# SCH_HomeConv2_mit-IR_2026-09-25.net
KiCad netlist of a schematic drawn in EasyEDA
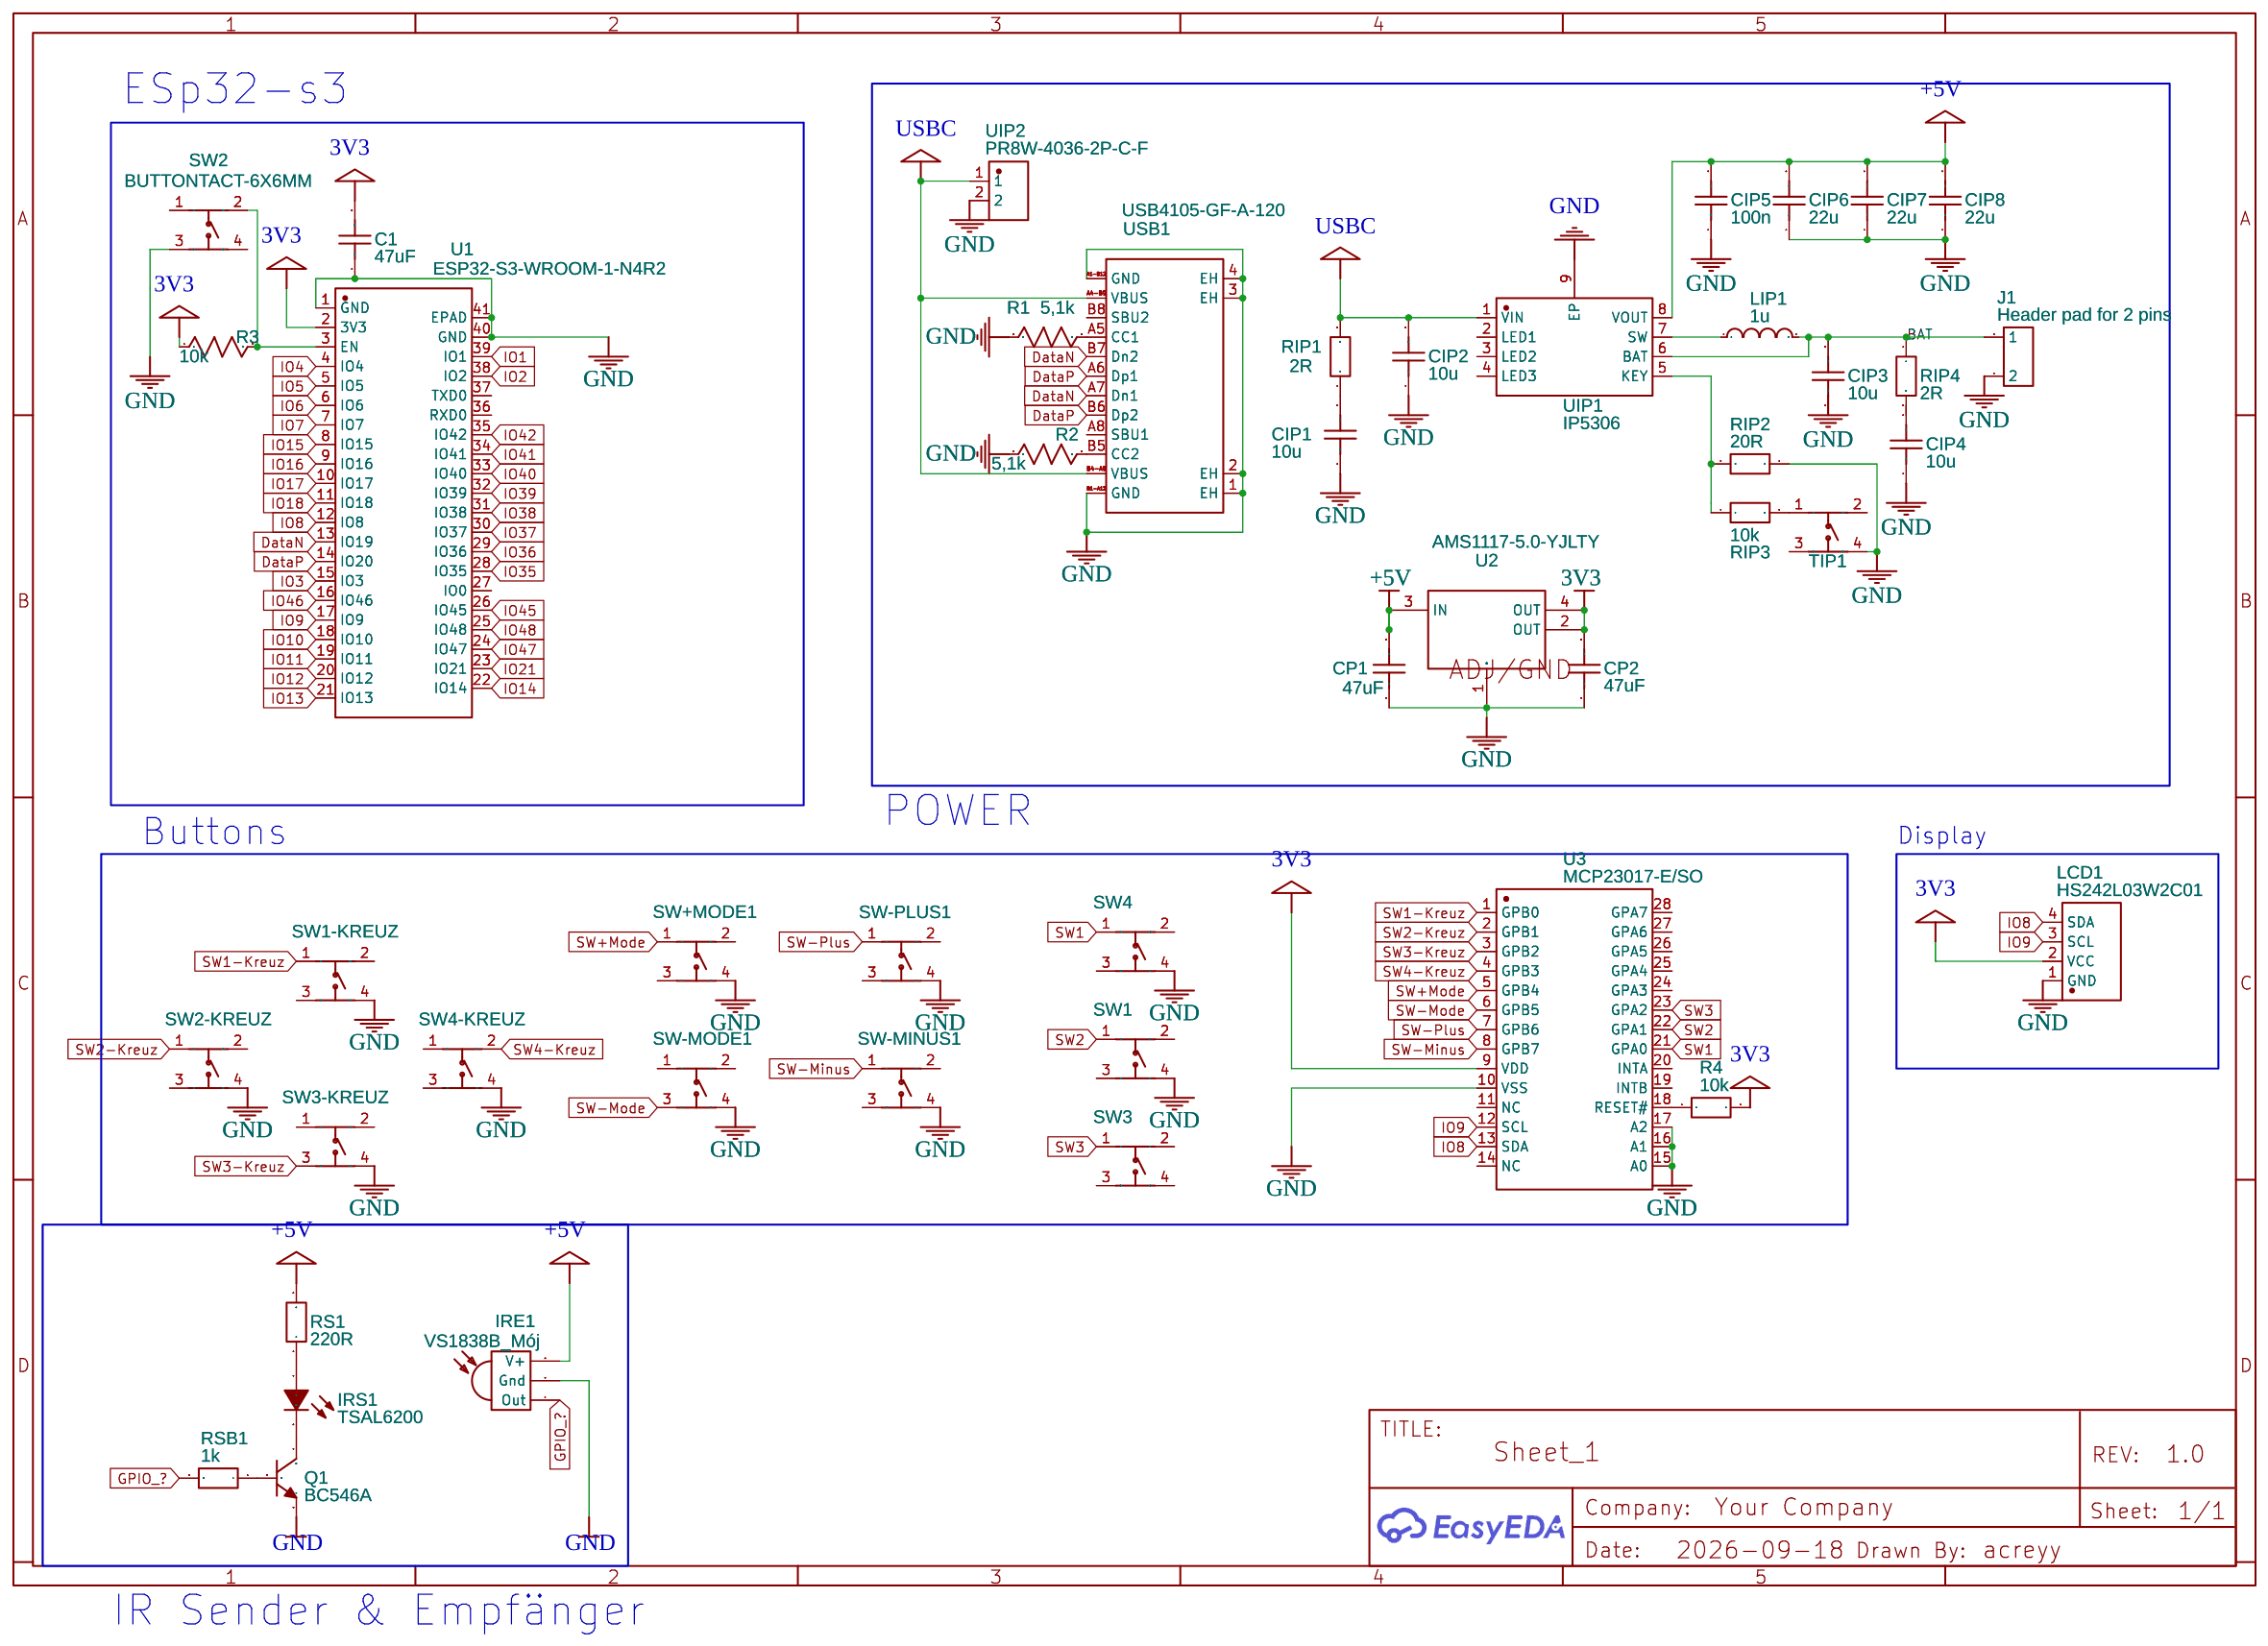
[diagram p0: schematic sheet]

(export (version "E")
  (design (tool "Eeschema 10.0.6"))
  (components
    (comp (ref "C1") (value "47uF") (libsource (lib "") (part "C_0805_US")))
    (comp (ref "CIP1") (value "10u") (libsource (lib "") (part "C_0805_US_1")))
    (comp (ref "CIP2") (value "10u") (libsource (lib "") (part "C_0805_US_1")))
    (comp (ref "CIP3") (value "10u") (libsource (lib "") (part "C_0805_US_1")))
    (comp (ref "CIP4") (value "10u") (libsource (lib "") (part "C_0805_US_1")))
    (comp (ref "CIP5") (value "100n") (libsource (lib "") (part "C_0805_US_1")))
    (comp (ref "CIP6") (value "22u") (libsource (lib "") (part "C_0805_US_1")))
    (comp (ref "CIP7") (value "22u") (libsource (lib "") (part "C_0805_US_1")))
    (comp (ref "CIP8") (value "22u") (libsource (lib "") (part "C_0805_US_1")))
    (comp (ref "CP1") (value "47uF") (libsource (lib "") (part "C_0805_US_2")))
    (comp (ref "CP2") (value "47uF") (libsource (lib "") (part "C_0805_US_2")))
    (comp (ref "IRE1") (value "VS1838B_Mój") (libsource (lib "") (part "VS1838B_Mój")))
    (comp (ref "IRS1")
      (value "TSAL6200")
      (fields (field (name "Manufacturer") "VISHAY(威世)"))
      (libsource (lib "") (part "TSAL6200"))
    )
    (comp (ref "J1")
      (value "Header pad for 2 pins")
      (fields
        (field (name "Manufacturer Part") "Female headerHDR1X8-2.54")
        (field (name "Manufacturer") "BOOMELE")
      )
      (libsource (lib "") (part "HEADER PAD 2X"))
    )
    (comp (ref "LCD1")
      (value "HS242L03W2C01")
      (fields (field (name "Manufacturer") "HS(汉昇)"))
      (libsource (lib "") (part "HS242L03W2C01"))
    )
    (comp (ref "LIP1") (value "1u") (libsource (lib "") (part "L_AXIAL-0.4_US")))
    (comp (ref "Q1")
      (value "BC546A")
      (fields (field (name "Manufacturer") "onsemi(安森美)"))
      (libsource (lib "") (part "BC546A"))
    )
    (comp (ref "R1") (value "5,1k") (libsource (lib "") (part "R_0805_US")))
    (comp (ref "R2") (value "5,1k") (libsource (lib "") (part "R_0805_US")))
    (comp (ref "R3") (value "10k") (libsource (lib "") (part "R_0805_US")))
    (comp (ref "R4") (value "10k") (libsource (lib "") (part "R_0805_EU_2")))
    (comp (ref "RIP1") (value "2R") (libsource (lib "") (part "R_0603_EU_2")))
    (comp (ref "RIP2") (value "20R") (libsource (lib "") (part "R_0603_EU_1")))
    (comp (ref "RIP3") (value "10k") (libsource (lib "") (part "R_0603_EU_3")))
    (comp (ref "RIP4") (value "2R") (libsource (lib "") (part "R_0603_EU")))
    (comp (ref "RS1") (value "220R") (libsource (lib "") (part "R_0805_EU")))
    (comp (ref "RSB1") (value "1k") (libsource (lib "") (part "R_0805_EU_1")))
    (comp (ref "SW+MODE1")
      (value "BUTTONTACT-6X6MM")
      (fields (field (name "Manufacturer Part") "Buttontact-6x6mm"))
      (libsource (lib "") (part "BUTTONTACT-6X6MM"))
    )
    (comp (ref "SW-MINUS1")
      (value "BUTTONTACT-6X6MM")
      (fields (field (name "Manufacturer Part") "Buttontact-6x6mm"))
      (libsource (lib "") (part "BUTTONTACT-6X6MM_5"))
    )
    (comp (ref "SW-MODE1")
      (value "BUTTONTACT-6X6MM")
      (fields (field (name "Manufacturer Part") "Buttontact-6x6mm"))
      (libsource (lib "") (part "BUTTONTACT-6X6MM_4"))
    )
    (comp (ref "SW-PLUS1")
      (value "BUTTONTACT-6X6MM")
      (fields (field (name "Manufacturer Part") "Buttontact-6x6mm"))
      (libsource (lib "") (part "BUTTONTACT-6X6MM_8"))
    )
    (comp (ref "SW1")
      (value "BUTTONTACT-6X6MM")
      (fields (field (name "Manufacturer Part") "Buttontact-6x6mm"))
      (libsource (lib "") (part "BUTTONTACT-6X6MM_2"))
    )
    (comp (ref "SW1-KREUZ")
      (value "BUTTONTACT-6X6MM")
      (fields (field (name "Manufacturer Part") "Buttontact-6x6mm"))
      (libsource (lib "") (part "BUTTONTACT-6X6MM_3"))
    )
    (comp (ref "SW2")
      (value "BUTTONTACT-6X6MM")
      (fields (field (name "Manufacturer Part") "Buttontact-6x6mm"))
      (libsource (lib "") (part "BUTTONTACT-6X6MM_2"))
    )
    (comp (ref "SW2-KREUZ")
      (value "BUTTONTACT-6X6MM")
      (fields (field (name "Manufacturer Part") "Buttontact-6x6mm"))
      (libsource (lib "") (part "BUTTONTACT-6X6MM_1"))
    )
    (comp (ref "SW3")
      (value "BUTTONTACT-6X6MM")
      (fields (field (name "Manufacturer Part") "Buttontact-6x6mm"))
      (libsource (lib "") (part "BUTTONTACT-6X6MM_2"))
    )
    (comp (ref "SW3-KREUZ")
      (value "BUTTONTACT-6X6MM")
      (fields (field (name "Manufacturer Part") "Buttontact-6x6mm"))
      (libsource (lib "") (part "BUTTONTACT-6X6MM_9"))
    )
    (comp (ref "SW4")
      (value "BUTTONTACT-6X6MM")
      (fields (field (name "Manufacturer Part") "Buttontact-6x6mm"))
      (libsource (lib "") (part "BUTTONTACT-6X6MM_2"))
    )
    (comp (ref "SW4-KREUZ")
      (value "BUTTONTACT-6X6MM")
      (fields (field (name "Manufacturer Part") "Buttontact-6x6mm"))
      (libsource (lib "") (part "BUTTONTACT-6X6MM_7"))
    )
    (comp (ref "TIP1")
      (value "BUTTONTACT-6X6MM")
      (fields (field (name "Manufacturer Part") "Buttontact-6x6mm"))
      (libsource (lib "") (part "BUTTONTACT-6X6MM_6"))
    )
    (comp (ref "U1")
      (value "ESP32-S3-WROOM-1-N4R2")
      (fields (field (name "Manufacturer") "ESPRESSIF(乐鑫)"))
      (libsource (lib "") (part "ESP32-S3-WROOM-1-N4R2"))
    )
    (comp (ref "U2") (value "AMS1117-5.0-YJLTY") (libsource (lib "") (part "AMS1117-5.0-YJLTY")))
    (comp (ref "U3")
      (value "MCP23017-E/SO")
      (fields (field (name "Manufacturer") "MICROCHIP(美国微芯)"))
      (libsource (lib "") (part "MCP23017-E/SO"))
    )
    (comp (ref "UIP1")
      (value "IP5306")
      (fields (field (name "Manufacturer") "INJOINIC(英集芯)"))
      (libsource (lib "") (part "IP5306"))
    )
    (comp (ref "UIP2")
      (value "PR8W-4036-2P-C-F")
      (fields (field (name "Manufacturer") "SAMZO(三佐)"))
      (libsource (lib "") (part "PR8W-4036-2P-C-F"))
    )
    (comp (ref "USB1")
      (value "USB4105-GF-A-120")
      (fields (field (name "Manufacturer") "GCT"))
      (libsource (lib "") (part "USB4105-GF-A-120"))
    )
  )
  (nets
    (net (code "1") (name "+5V") (class "Default")
      (node (ref "CIP5") (pin "2") (pinfunction "2_2") (pintype "unspecified"))
      (node (ref "CIP6") (pin "2") (pinfunction "2_2") (pintype "unspecified"))
      (node (ref "CIP7") (pin "2") (pinfunction "2_2") (pintype "unspecified"))
      (node (ref "CIP8") (pin "2") (pinfunction "2_2") (pintype "unspecified"))
      (node (ref "CP1") (pin "2") (pinfunction "2_2") (pintype "unspecified"))
      (node (ref "IRE1") (pin "3") (pinfunction "V+_3") (pintype "bidirectional"))
      (node (ref "RS1") (pin "2") (pinfunction "2_2") (pintype "unspecified"))
      (node (ref "U2") (pin "3") (pinfunction "IN_3") (pintype "passive"))
      (node (ref "UIP1") (pin "8") (pinfunction "VOUT_8") (pintype "unspecified"))
    )
    (net (code "2") (name "/BAT") (class "Default")
      (node (ref "CIP3") (pin "2") (pinfunction "2_2") (pintype "unspecified"))
      (node (ref "J1") (pin "1") (pinfunction "1_1") (pintype "unspecified"))
      (node (ref "LIP1") (pin "2") (pinfunction "2_2") (pintype "unspecified"))
      (node (ref "RIP4") (pin "1") (pinfunction "1_1") (pintype "unspecified"))
      (node (ref "UIP1") (pin "6") (pinfunction "BAT_6") (pintype "unspecified"))
    )
    (net (code "3") (name "3V3") (class "Default")
      (node (ref "C1") (pin "2") (pinfunction "2_2") (pintype "unspecified"))
      (node (ref "CP2") (pin "2") (pinfunction "2_2") (pintype "unspecified"))
      (node (ref "LCD1") (pin "2") (pinfunction "VCC_2") (pintype "unspecified"))
      (node (ref "R3") (pin "1") (pinfunction "1_1") (pintype "unspecified"))
      (node (ref "R4") (pin "2") (pinfunction "2_2") (pintype "unspecified"))
      (node (ref "U1") (pin "2") (pinfunction "3V3_2") (pintype "unspecified"))
      (node (ref "U2") (pin "2") (pinfunction "OUT_2") (pintype "passive"))
      (node (ref "U2") (pin "4") (pinfunction "OUT_4") (pintype "passive"))
      (node (ref "U3") (pin "9") (pinfunction "VDD_9") (pintype "unspecified"))
    )
    (net (code "4") (name "DataN") (class "Default")
      (node (ref "U1") (pin "13") (pinfunction "IO19_13") (pintype "unspecified"))
      (node (ref "USB1") (pin "A7") (pinfunction "Dn1_A7") (pintype "unspecified"))
      (node (ref "USB1") (pin "B7") (pinfunction "Dn2_B7") (pintype "unspecified"))
    )
    (net (code "5") (name "DataP") (class "Default")
      (node (ref "U1") (pin "14") (pinfunction "IO20_14") (pintype "unspecified"))
      (node (ref "USB1") (pin "A6") (pinfunction "Dp1_A6") (pintype "unspecified"))
      (node (ref "USB1") (pin "B6") (pinfunction "Dp2_B6") (pintype "unspecified"))
    )
    (net (code "6") (name "GND") (class "Default")
      (node (ref "C1") (pin "1") (pinfunction "1_1") (pintype "unspecified"))
      (node (ref "CIP1") (pin "1") (pinfunction "1_1") (pintype "unspecified"))
      (node (ref "CIP2") (pin "1") (pinfunction "1_1") (pintype "unspecified"))
      (node (ref "CIP4") (pin "1") (pinfunction "1_1") (pintype "unspecified"))
      (node (ref "CIP5") (pin "1") (pinfunction "1_1") (pintype "unspecified"))
      (node (ref "CIP6") (pin "1") (pinfunction "1_1") (pintype "unspecified"))
      (node (ref "CIP7") (pin "1") (pinfunction "1_1") (pintype "unspecified"))
      (node (ref "CIP8") (pin "1") (pinfunction "1_1") (pintype "unspecified"))
      (node (ref "CP1") (pin "1") (pinfunction "1_1") (pintype "unspecified"))
      (node (ref "CP2") (pin "1") (pinfunction "1_1") (pintype "unspecified"))
      (node (ref "IRE1") (pin "2") (pinfunction "Gnd_2") (pintype "bidirectional"))
      (node (ref "J1") (pin "2") (pinfunction "2_2") (pintype "unspecified"))
      (node (ref "LCD1") (pin "1") (pinfunction "GND_1") (pintype "unspecified"))
      (node (ref "Q1") (pin "3") (pinfunction "E_3") (pintype "input"))
      (node (ref "R1") (pin "1") (pinfunction "1_1") (pintype "unspecified"))
      (node (ref "R2") (pin "1") (pinfunction "1_1") (pintype "unspecified"))
      (node (ref "RIP2") (pin "1") (pinfunction "1_1") (pintype "unspecified"))
      (node (ref "SW+MODE1") (pin "4") (pinfunction "D_4") (pintype "unspecified"))
      (node (ref "SW-MINUS1") (pin "4") (pinfunction "D_4") (pintype "unspecified"))
      (node (ref "SW-MODE1") (pin "4") (pinfunction "D_4") (pintype "unspecified"))
      (node (ref "SW-PLUS1") (pin "4") (pinfunction "D_4") (pintype "unspecified"))
      (node (ref "SW1") (pin "4") (pinfunction "D_4") (pintype "unspecified"))
      (node (ref "SW1-KREUZ") (pin "4") (pinfunction "D_4") (pintype "unspecified"))
      (node (ref "SW2") (pin "3") (pinfunction "C_3") (pintype "unspecified"))
      (node (ref "SW2-KREUZ") (pin "4") (pinfunction "D_4") (pintype "unspecified"))
      (node (ref "SW3-KREUZ") (pin "4") (pinfunction "D_4") (pintype "unspecified"))
      (node (ref "SW4") (pin "4") (pinfunction "D_4") (pintype "unspecified"))
      (node (ref "SW4-KREUZ") (pin "4") (pinfunction "D_4") (pintype "unspecified"))
      (node (ref "TIP1") (pin "4") (pinfunction "D_4") (pintype "unspecified"))
      (node (ref "U1") (pin "1") (pinfunction "GND_1") (pintype "unspecified"))
      (node (ref "U1") (pin "40") (pinfunction "GND_40") (pintype "unspecified"))
      (node (ref "U1") (pin "41") (pinfunction "EPAD_41") (pintype "unspecified"))
      (node (ref "U2") (pin "1") (pinfunction "ADJ/GND_1") (pintype "passive"))
      (node (ref "U3") (pin "10") (pinfunction "VSS_10") (pintype "unspecified"))
      (node (ref "U3") (pin "15") (pinfunction "A0_15") (pintype "unspecified"))
      (node (ref "U3") (pin "16") (pinfunction "A1_16") (pintype "unspecified"))
      (node (ref "U3") (pin "17") (pinfunction "A2_17") (pintype "unspecified"))
      (node (ref "UIP1") (pin "9") (pinfunction "EP_9") (pintype "unspecified"))
      (node (ref "UIP2") (pin "2") (pinfunction "2_2") (pintype "unspecified"))
      (node (ref "USB1") (pin "1") (pinfunction "EH_1") (pintype "unspecified"))
      (node (ref "USB1") (pin "2") (pinfunction "EH_2") (pintype "unspecified"))
      (node (ref "USB1") (pin "3") (pinfunction "EH_3") (pintype "unspecified"))
      (node (ref "USB1") (pin "4") (pinfunction "EH_4") (pintype "unspecified"))
      (node (ref "USB1") (pin "A1-B12") (pinfunction "GND_A1-B12") (pintype "unspecified"))
      (node (ref "USB1") (pin "B1-A12") (pinfunction "GND_B1-A12") (pintype "unspecified"))
    )
    (net (code "7") (name "GPIO_?") (class "Default")
      (node (ref "IRE1") (pin "1") (pinfunction "Out_1") (pintype "bidirectional"))
      (node (ref "RSB1") (pin "2") (pinfunction "2_2") (pintype "unspecified"))
    )
    (net (code "8") (name "IO1") (class "Default")
      (node (ref "U1") (pin "39") (pinfunction "IO1_39") (pintype "unspecified"))
    )
    (net (code "9") (name "IO2") (class "Default")
      (node (ref "U1") (pin "38") (pinfunction "IO2_38") (pintype "unspecified"))
    )
    (net (code "10") (name "IO3") (class "Default")
      (node (ref "U1") (pin "15") (pinfunction "IO3_15") (pintype "unspecified"))
    )
    (net (code "11") (name "IO4") (class "Default")
      (node (ref "U1") (pin "4") (pinfunction "IO4_4") (pintype "unspecified"))
    )
    (net (code "12") (name "IO5") (class "Default")
      (node (ref "U1") (pin "5") (pinfunction "IO5_5") (pintype "unspecified"))
    )
    (net (code "13") (name "IO6") (class "Default")
      (node (ref "U1") (pin "6") (pinfunction "IO6_6") (pintype "unspecified"))
    )
    (net (code "14") (name "IO7") (class "Default")
      (node (ref "U1") (pin "7") (pinfunction "IO7_7") (pintype "unspecified"))
    )
    (net (code "15") (name "IO8") (class "Default")
      (node (ref "LCD1") (pin "4") (pinfunction "SDA_4") (pintype "unspecified"))
      (node (ref "U1") (pin "12") (pinfunction "IO8_12") (pintype "unspecified"))
      (node (ref "U3") (pin "13") (pinfunction "SDA_13") (pintype "unspecified"))
    )
    (net (code "16") (name "IO9") (class "Default")
      (node (ref "LCD1") (pin "3") (pinfunction "SCL_3") (pintype "unspecified"))
      (node (ref "U1") (pin "17") (pinfunction "IO9_17") (pintype "unspecified"))
      (node (ref "U3") (pin "12") (pinfunction "SCL_12") (pintype "unspecified"))
    )
    (net (code "17") (name "IO10") (class "Default")
      (node (ref "U1") (pin "18") (pinfunction "IO10_18") (pintype "unspecified"))
    )
    (net (code "18") (name "IO11") (class "Default")
      (node (ref "U1") (pin "19") (pinfunction "IO11_19") (pintype "unspecified"))
    )
    (net (code "19") (name "IO12") (class "Default")
      (node (ref "U1") (pin "20") (pinfunction "IO12_20") (pintype "unspecified"))
    )
    (net (code "20") (name "IO13") (class "Default")
      (node (ref "U1") (pin "21") (pinfunction "IO13_21") (pintype "unspecified"))
    )
    (net (code "21") (name "IO14") (class "Default")
      (node (ref "U1") (pin "22") (pinfunction "IO14_22") (pintype "unspecified"))
    )
    (net (code "22") (name "IO15") (class "Default")
      (node (ref "U1") (pin "8") (pinfunction "IO15_8") (pintype "unspecified"))
    )
    (net (code "23") (name "IO16") (class "Default")
      (node (ref "U1") (pin "9") (pinfunction "IO16_9") (pintype "unspecified"))
    )
    (net (code "24") (name "IO17") (class "Default")
      (node (ref "U1") (pin "10") (pinfunction "IO17_10") (pintype "unspecified"))
    )
    (net (code "25") (name "IO18") (class "Default")
      (node (ref "U1") (pin "11") (pinfunction "IO18_11") (pintype "unspecified"))
    )
    (net (code "26") (name "IO21") (class "Default")
      (node (ref "U1") (pin "23") (pinfunction "IO21_23") (pintype "unspecified"))
    )
    (net (code "27") (name "IO35") (class "Default")
      (node (ref "U1") (pin "28") (pinfunction "IO35_28") (pintype "unspecified"))
    )
    (net (code "28") (name "IO36") (class "Default")
      (node (ref "U1") (pin "29") (pinfunction "IO36_29") (pintype "unspecified"))
    )
    (net (code "29") (name "IO37") (class "Default")
      (node (ref "U1") (pin "30") (pinfunction "IO37_30") (pintype "unspecified"))
    )
    (net (code "30") (name "IO38") (class "Default")
      (node (ref "U1") (pin "31") (pinfunction "IO38_31") (pintype "unspecified"))
    )
    (net (code "31") (name "IO39") (class "Default")
      (node (ref "U1") (pin "32") (pinfunction "IO39_32") (pintype "unspecified"))
    )
    (net (code "32") (name "IO40") (class "Default")
      (node (ref "U1") (pin "33") (pinfunction "IO40_33") (pintype "unspecified"))
    )
    (net (code "33") (name "IO41") (class "Default")
      (node (ref "U1") (pin "34") (pinfunction "IO41_34") (pintype "unspecified"))
    )
    (net (code "34") (name "IO42") (class "Default")
      (node (ref "U1") (pin "35") (pinfunction "IO42_35") (pintype "unspecified"))
    )
    (net (code "35") (name "IO45") (class "Default")
      (node (ref "U1") (pin "26") (pinfunction "IO45_26") (pintype "unspecified"))
    )
    (net (code "36") (name "IO46") (class "Default")
      (node (ref "U1") (pin "16") (pinfunction "IO46_16") (pintype "unspecified"))
    )
    (net (code "37") (name "IO47") (class "Default")
      (node (ref "U1") (pin "24") (pinfunction "IO47_24") (pintype "unspecified"))
    )
    (net (code "38") (name "IO48") (class "Default")
      (node (ref "U1") (pin "25") (pinfunction "IO48_25") (pintype "unspecified"))
    )
    (net (code "39") (name "Net-(CIP1-Pad2)") (class "Default")
      (node (ref "CIP1") (pin "2") (pinfunction "2_2") (pintype "unspecified"))
      (node (ref "RIP1") (pin "1") (pinfunction "1_1") (pintype "unspecified"))
    )
    (net (code "40") (name "Net-(IRS1-A)") (class "Default")
      (node (ref "IRS1") (pin "1") (pinfunction "A_1") (pintype "input"))
      (node (ref "RS1") (pin "1") (pinfunction "1_1") (pintype "unspecified"))
    )
    (net (code "41") (name "Net-(IRS1-C)") (class "Default")
      (node (ref "IRS1") (pin "2") (pinfunction "C_2") (pintype "input"))
      (node (ref "Q1") (pin "1") (pinfunction "C_1") (pintype "input"))
    )
    (net (code "42") (name "Net-(Q1-B)") (class "Default")
      (node (ref "Q1") (pin "2") (pinfunction "B_2") (pintype "input"))
      (node (ref "RSB1") (pin "1") (pinfunction "1_1") (pintype "unspecified"))
    )
    (net (code "43") (name "Net-(SW2-B)") (class "Default")
      (node (ref "R3") (pin "2") (pinfunction "2_2") (pintype "unspecified"))
      (node (ref "SW2") (pin "2") (pinfunction "B_2") (pintype "unspecified"))
      (node (ref "U1") (pin "3") (pinfunction "EN_3") (pintype "unspecified"))
    )
    (net (code "44") (name "Net-(TIP1-A)") (class "Default")
      (node (ref "RIP3") (pin "2") (pinfunction "2_2") (pintype "unspecified"))
      (node (ref "TIP1") (pin "1") (pinfunction "A_1") (pintype "unspecified"))
    )
    (net (code "45") (name "Net-(U3-RESET#)") (class "Default")
      (node (ref "R4") (pin "1") (pinfunction "1_1") (pintype "unspecified"))
      (node (ref "U3") (pin "18") (pinfunction "RESET#_18") (pintype "unspecified"))
    )
    (net (code "46") (name "Net-(UIP1-KEY)") (class "Default")
      (node (ref "RIP2") (pin "2") (pinfunction "2_2") (pintype "unspecified"))
      (node (ref "RIP3") (pin "1") (pinfunction "1_1") (pintype "unspecified"))
      (node (ref "UIP1") (pin "5") (pinfunction "KEY_5") (pintype "unspecified"))
    )
    (net (code "47") (name "Net-(UIP1-SW)") (class "Default")
      (node (ref "LIP1") (pin "1") (pinfunction "1_1") (pintype "unspecified"))
      (node (ref "UIP1") (pin "7") (pinfunction "SW_7") (pintype "unspecified"))
    )
    (net (code "48") (name "Net-(USB1-CC1)") (class "Default")
      (node (ref "R1") (pin "2") (pinfunction "2_2") (pintype "unspecified"))
      (node (ref "USB1") (pin "A5") (pinfunction "CC1_A5") (pintype "unspecified"))
    )
    (net (code "49") (name "Net-(USB1-CC2)") (class "Default")
      (node (ref "R2") (pin "2") (pinfunction "2_2") (pintype "unspecified"))
      (node (ref "USB1") (pin "B5") (pinfunction "CC2_B5") (pintype "unspecified"))
    )
    (net (code "50") (name "SW+Mode") (class "Default")
      (node (ref "SW+MODE1") (pin "1") (pinfunction "A_1") (pintype "unspecified"))
      (node (ref "U3") (pin "5") (pinfunction "GPB4_5") (pintype "unspecified"))
    )
    (net (code "51") (name "SW-Minus") (class "Default")
      (node (ref "SW-MINUS1") (pin "1") (pinfunction "A_1") (pintype "unspecified"))
      (node (ref "U3") (pin "8") (pinfunction "GPB7_8") (pintype "unspecified"))
    )
    (net (code "52") (name "SW-Mode") (class "Default")
      (node (ref "SW-MODE1") (pin "3") (pinfunction "C_3") (pintype "unspecified"))
      (node (ref "U3") (pin "6") (pinfunction "GPB5_6") (pintype "unspecified"))
    )
    (net (code "53") (name "SW-Plus") (class "Default")
      (node (ref "SW-PLUS1") (pin "1") (pinfunction "A_1") (pintype "unspecified"))
      (node (ref "U3") (pin "7") (pinfunction "GPB6_7") (pintype "unspecified"))
    )
    (net (code "54") (name "SW1") (class "Default")
      (node (ref "SW4") (pin "1") (pinfunction "A_1") (pintype "unspecified"))
      (node (ref "U3") (pin "21") (pinfunction "GPA0_21") (pintype "unspecified"))
    )
    (net (code "55") (name "SW1-Kreuz") (class "Default")
      (node (ref "SW1-KREUZ") (pin "1") (pinfunction "A_1") (pintype "unspecified"))
      (node (ref "U3") (pin "1") (pinfunction "GPB0_1") (pintype "unspecified"))
    )
    (net (code "56") (name "SW2") (class "Default")
      (node (ref "SW1") (pin "1") (pinfunction "A_1") (pintype "unspecified"))
      (node (ref "U3") (pin "22") (pinfunction "GPA1_22") (pintype "unspecified"))
    )
    (net (code "57") (name "SW2-Kreuz") (class "Default")
      (node (ref "SW2-KREUZ") (pin "1") (pinfunction "A_1") (pintype "unspecified"))
      (node (ref "U3") (pin "2") (pinfunction "GPB1_2") (pintype "unspecified"))
    )
    (net (code "58") (name "SW3") (class "Default")
      (node (ref "SW3") (pin "1") (pinfunction "A_1") (pintype "unspecified"))
      (node (ref "U3") (pin "23") (pinfunction "GPA2_23") (pintype "unspecified"))
    )
    (net (code "59") (name "SW3-Kreuz") (class "Default")
      (node (ref "SW3-KREUZ") (pin "3") (pinfunction "C_3") (pintype "unspecified"))
      (node (ref "U3") (pin "3") (pinfunction "GPB2_3") (pintype "unspecified"))
    )
    (net (code "60") (name "SW4-Kreuz") (class "Default")
      (node (ref "SW4-KREUZ") (pin "2") (pinfunction "B_2") (pintype "unspecified"))
      (node (ref "U3") (pin "4") (pinfunction "GPB3_4") (pintype "unspecified"))
    )
    (net (code "61") (name "USBC") (class "Default")
      (node (ref "CIP2") (pin "2") (pinfunction "2_2") (pintype "unspecified"))
      (node (ref "RIP1") (pin "2") (pinfunction "2_2") (pintype "unspecified"))
      (node (ref "UIP1") (pin "1") (pinfunction "VIN_1") (pintype "unspecified"))
      (node (ref "UIP2") (pin "1") (pinfunction "1_1") (pintype "unspecified"))
      (node (ref "USB1") (pin "A4-B9") (pinfunction "VBUS_A4-B9") (pintype "unspecified"))
      (node (ref "USB1") (pin "B4-A9") (pinfunction "VBUS_B4-A9") (pintype "unspecified"))
    )
    (net (code "62") (name "unconnected-(CIP3-Pad1)") (class "Default")
      (node (ref "CIP3") (pin "1") (pinfunction "1_1") (pintype "unspecified"))
    )
    (net (code "63") (name "unconnected-(CIP4-Pad2)") (class "Default")
      (node (ref "CIP4") (pin "2") (pinfunction "2_2") (pintype "unspecified"))
    )
    (net (code "64") (name "unconnected-(RIP4-Pad2)") (class "Default")
      (node (ref "RIP4") (pin "2") (pinfunction "2_2") (pintype "unspecified"))
    )
    (net (code "65") (name "unconnected-(SW+MODE1-B-Pad2)") (class "Default")
      (node (ref "SW+MODE1") (pin "2") (pinfunction "B_2") (pintype "unspecified"))
    )
    (net (code "66") (name "unconnected-(SW+MODE1-C-Pad3)") (class "Default")
      (node (ref "SW+MODE1") (pin "3") (pinfunction "C_3") (pintype "unspecified"))
    )
    (net (code "67") (name "unconnected-(SW-MINUS1-B-Pad2)") (class "Default")
      (node (ref "SW-MINUS1") (pin "2") (pinfunction "B_2") (pintype "unspecified"))
    )
    (net (code "68") (name "unconnected-(SW-MINUS1-C-Pad3)") (class "Default")
      (node (ref "SW-MINUS1") (pin "3") (pinfunction "C_3") (pintype "unspecified"))
    )
    (net (code "69") (name "unconnected-(SW-MODE1-A-Pad1)") (class "Default")
      (node (ref "SW-MODE1") (pin "1") (pinfunction "A_1") (pintype "unspecified"))
    )
    (net (code "70") (name "unconnected-(SW-MODE1-B-Pad2)") (class "Default")
      (node (ref "SW-MODE1") (pin "2") (pinfunction "B_2") (pintype "unspecified"))
    )
    (net (code "71") (name "unconnected-(SW-PLUS1-B-Pad2)") (class "Default")
      (node (ref "SW-PLUS1") (pin "2") (pinfunction "B_2") (pintype "unspecified"))
    )
    (net (code "72") (name "unconnected-(SW-PLUS1-C-Pad3)") (class "Default")
      (node (ref "SW-PLUS1") (pin "3") (pinfunction "C_3") (pintype "unspecified"))
    )
    (net (code "73") (name "unconnected-(SW1-B-Pad2)") (class "Default")
      (node (ref "SW1") (pin "2") (pinfunction "B_2") (pintype "unspecified"))
    )
    (net (code "74") (name "unconnected-(SW1-C-Pad3)") (class "Default")
      (node (ref "SW1") (pin "3") (pinfunction "C_3") (pintype "unspecified"))
    )
    (net (code "75") (name "unconnected-(SW1-KREUZ-B-Pad2)") (class "Default")
      (node (ref "SW1-KREUZ") (pin "2") (pinfunction "B_2") (pintype "unspecified"))
    )
    (net (code "76") (name "unconnected-(SW1-KREUZ-C-Pad3)") (class "Default")
      (node (ref "SW1-KREUZ") (pin "3") (pinfunction "C_3") (pintype "unspecified"))
    )
    (net (code "77") (name "unconnected-(SW2-A-Pad1)") (class "Default")
      (node (ref "SW2") (pin "1") (pinfunction "A_1") (pintype "unspecified"))
    )
    (net (code "78") (name "unconnected-(SW2-D-Pad4)") (class "Default")
      (node (ref "SW2") (pin "4") (pinfunction "D_4") (pintype "unspecified"))
    )
    (net (code "79") (name "unconnected-(SW2-KREUZ-B-Pad2)") (class "Default")
      (node (ref "SW2-KREUZ") (pin "2") (pinfunction "B_2") (pintype "unspecified"))
    )
    (net (code "80") (name "unconnected-(SW2-KREUZ-C-Pad3)") (class "Default")
      (node (ref "SW2-KREUZ") (pin "3") (pinfunction "C_3") (pintype "unspecified"))
    )
    (net (code "81") (name "unconnected-(SW3-B-Pad2)") (class "Default")
      (node (ref "SW3") (pin "2") (pinfunction "B_2") (pintype "unspecified"))
    )
    (net (code "82") (name "unconnected-(SW3-C-Pad3)") (class "Default")
      (node (ref "SW3") (pin "3") (pinfunction "C_3") (pintype "unspecified"))
    )
    (net (code "83") (name "unconnected-(SW3-D-Pad4)") (class "Default")
      (node (ref "SW3") (pin "4") (pinfunction "D_4") (pintype "unspecified"))
    )
    (net (code "84") (name "unconnected-(SW3-KREUZ-A-Pad1)") (class "Default")
      (node (ref "SW3-KREUZ") (pin "1") (pinfunction "A_1") (pintype "unspecified"))
    )
    (net (code "85") (name "unconnected-(SW3-KREUZ-B-Pad2)") (class "Default")
      (node (ref "SW3-KREUZ") (pin "2") (pinfunction "B_2") (pintype "unspecified"))
    )
    (net (code "86") (name "unconnected-(SW4-B-Pad2)") (class "Default")
      (node (ref "SW4") (pin "2") (pinfunction "B_2") (pintype "unspecified"))
    )
    (net (code "87") (name "unconnected-(SW4-C-Pad3)") (class "Default")
      (node (ref "SW4") (pin "3") (pinfunction "C_3") (pintype "unspecified"))
    )
    (net (code "88") (name "unconnected-(SW4-KREUZ-A-Pad1)") (class "Default")
      (node (ref "SW4-KREUZ") (pin "1") (pinfunction "A_1") (pintype "unspecified"))
    )
    (net (code "89") (name "unconnected-(SW4-KREUZ-C-Pad3)") (class "Default")
      (node (ref "SW4-KREUZ") (pin "3") (pinfunction "C_3") (pintype "unspecified"))
    )
    (net (code "90") (name "unconnected-(TIP1-B-Pad2)") (class "Default")
      (node (ref "TIP1") (pin "2") (pinfunction "B_2") (pintype "unspecified"))
    )
    (net (code "91") (name "unconnected-(TIP1-C-Pad3)") (class "Default")
      (node (ref "TIP1") (pin "3") (pinfunction "C_3") (pintype "unspecified"))
    )
    (net (code "92") (name "unconnected-(U1-IO0-Pad27)") (class "Default")
      (node (ref "U1") (pin "27") (pinfunction "IO0_27") (pintype "unspecified"))
    )
    (net (code "93") (name "unconnected-(U1-RXD0-Pad36)") (class "Default")
      (node (ref "U1") (pin "36") (pinfunction "RXD0_36") (pintype "unspecified"))
    )
    (net (code "94") (name "unconnected-(U1-TXD0-Pad37)") (class "Default")
      (node (ref "U1") (pin "37") (pinfunction "TXD0_37") (pintype "unspecified"))
    )
    (net (code "95") (name "unconnected-(U3-GPA3-Pad24)") (class "Default")
      (node (ref "U3") (pin "24") (pinfunction "GPA3_24") (pintype "unspecified"))
    )
    (net (code "96") (name "unconnected-(U3-GPA4-Pad25)") (class "Default")
      (node (ref "U3") (pin "25") (pinfunction "GPA4_25") (pintype "unspecified"))
    )
    (net (code "97") (name "unconnected-(U3-GPA5-Pad26)") (class "Default")
      (node (ref "U3") (pin "26") (pinfunction "GPA5_26") (pintype "unspecified"))
    )
    (net (code "98") (name "unconnected-(U3-GPA6-Pad27)") (class "Default")
      (node (ref "U3") (pin "27") (pinfunction "GPA6_27") (pintype "unspecified"))
    )
    (net (code "99") (name "unconnected-(U3-GPA7-Pad28)") (class "Default")
      (node (ref "U3") (pin "28") (pinfunction "GPA7_28") (pintype "unspecified"))
    )
    (net (code "100") (name "unconnected-(U3-INTA-Pad20)") (class "Default")
      (node (ref "U3") (pin "20") (pinfunction "INTA_20") (pintype "unspecified"))
    )
    (net (code "101") (name "unconnected-(U3-INTB-Pad19)") (class "Default")
      (node (ref "U3") (pin "19") (pinfunction "INTB_19") (pintype "unspecified"))
    )
    (net (code "102") (name "unconnected-(U3-NC-Pad11)") (class "Default")
      (node (ref "U3") (pin "11") (pinfunction "NC_11") (pintype "unspecified"))
    )
    (net (code "103") (name "unconnected-(U3-NC-Pad14)") (class "Default")
      (node (ref "U3") (pin "14") (pinfunction "NC_14") (pintype "unspecified"))
    )
    (net (code "104") (name "unconnected-(UIP1-LED1-Pad2)") (class "Default")
      (node (ref "UIP1") (pin "2") (pinfunction "LED1_2") (pintype "unspecified"))
    )
    (net (code "105") (name "unconnected-(UIP1-LED2-Pad3)") (class "Default")
      (node (ref "UIP1") (pin "3") (pinfunction "LED2_3") (pintype "unspecified"))
    )
    (net (code "106") (name "unconnected-(UIP1-LED3-Pad4)") (class "Default")
      (node (ref "UIP1") (pin "4") (pinfunction "LED3_4") (pintype "unspecified"))
    )
    (net (code "107") (name "unconnected-(USB1-SBU1-PadA8)") (class "Default")
      (node (ref "USB1") (pin "A8") (pinfunction "SBU1_A8") (pintype "unspecified"))
    )
    (net (code "108") (name "unconnected-(USB1-SBU2-PadB8)") (class "Default")
      (node (ref "USB1") (pin "B8") (pinfunction "SBU2_B8") (pintype "unspecified"))
    )
  )
)
